# POWER.net
KiCad netlist of a schematic drawn in Altium Designer
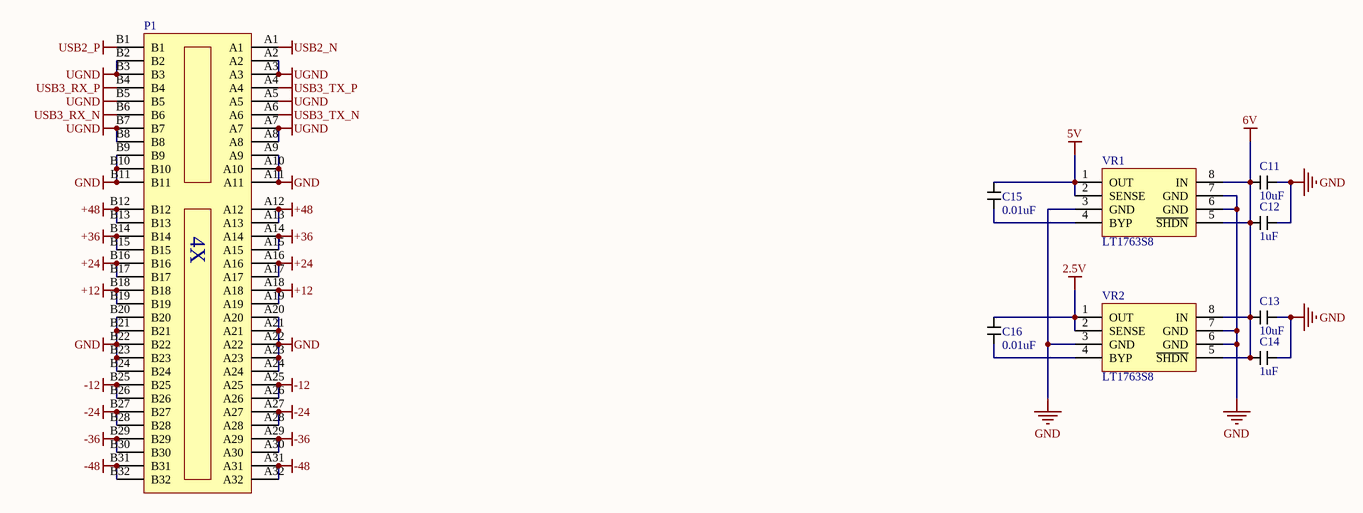
[diagram p0: POWER.SchDoc]

(export (version "E")
  (design (tool "Eeschema 10.0.6"))
  (components
    (comp (ref "C11") (value "10uF") (footprint "C0805") (libsource (lib "SMU") (part "C0805")))
    (comp (ref "C12") (value "1uF") (footprint "C0805") (libsource (lib "SMU") (part "C0805")))
    (comp (ref "C13") (value "10uF") (footprint "C0805") (libsource (lib "SMU") (part "C0805")))
    (comp (ref "C14") (value "1uF") (footprint "C0805") (libsource (lib "SMU") (part "C0805")))
    (comp (ref "C15") (value "0.01uF") (footprint "C0805") (libsource (lib "SMU") (part "C0805")))
    (comp (ref "C16") (value "0.01uF") (footprint "C0805") (libsource (lib "SMU") (part "C0805")))
    (comp (ref "P1")
      (value "10018783-10201TLF")
      (footprint "PCIe4X")
      (description "PCIe 4x")
      (libsource (lib "OpenSEM") (part "10018783-10201TLF"))
    )
    (comp (ref "VR1") (value "LT1763S8") (footprint "SOIC-8") (libsource (lib "OpenSEM") (part "LT1763S8")))
    (comp (ref "VR2") (value "LT1763S8") (footprint "SOIC-8") (libsource (lib "OpenSEM") (part "LT1763S8")))
  )
  (nets
    (net (code "1") (name "+12") (class "Default")
      (node (ref "P1") (pin "A18") (pinfunction "A18_A18") (pintype "passive"))
      (node (ref "P1") (pin "A19") (pinfunction "A19_A19") (pintype "passive"))
      (node (ref "P1") (pin "B18") (pinfunction "B18_B18") (pintype "passive"))
      (node (ref "P1") (pin "B19") (pinfunction "B19_B19") (pintype "passive"))
    )
    (net (code "2") (name "+24") (class "Default")
      (node (ref "P1") (pin "A16") (pinfunction "A16_A16") (pintype "passive"))
      (node (ref "P1") (pin "A17") (pinfunction "A17_A17") (pintype "passive"))
      (node (ref "P1") (pin "B16") (pinfunction "B16_B16") (pintype "passive"))
      (node (ref "P1") (pin "B17") (pinfunction "B17_B17") (pintype "passive"))
    )
    (net (code "3") (name "+36") (class "Default")
      (node (ref "P1") (pin "A14") (pinfunction "A14_A14") (pintype "passive"))
      (node (ref "P1") (pin "A15") (pinfunction "A15_A15") (pintype "passive"))
      (node (ref "P1") (pin "B14") (pinfunction "B14_B14") (pintype "passive"))
      (node (ref "P1") (pin "B15") (pinfunction "B15_B15") (pintype "passive"))
    )
    (net (code "4") (name "+48") (class "Default")
      (node (ref "P1") (pin "A12") (pinfunction "A12_A12") (pintype "passive"))
      (node (ref "P1") (pin "A13") (pinfunction "A13_A13") (pintype "passive"))
      (node (ref "P1") (pin "B12") (pinfunction "B12_B12") (pintype "passive"))
      (node (ref "P1") (pin "B13") (pinfunction "B13_B13") (pintype "passive"))
    )
    (net (code "5") (name "-12") (class "Default")
      (node (ref "P1") (pin "A25") (pinfunction "A25_A25") (pintype "passive"))
      (node (ref "P1") (pin "A26") (pinfunction "A26_A26") (pintype "passive"))
      (node (ref "P1") (pin "B25") (pinfunction "B25_B25") (pintype "passive"))
      (node (ref "P1") (pin "B26") (pinfunction "B26_B26") (pintype "passive"))
    )
    (net (code "6") (name "-24") (class "Default")
      (node (ref "P1") (pin "A27") (pinfunction "A27_A27") (pintype "passive"))
      (node (ref "P1") (pin "A28") (pinfunction "A28_A28") (pintype "passive"))
      (node (ref "P1") (pin "B27") (pinfunction "B27_B27") (pintype "passive"))
      (node (ref "P1") (pin "B28") (pinfunction "B28_B28") (pintype "passive"))
    )
    (net (code "7") (name "-36") (class "Default")
      (node (ref "P1") (pin "A29") (pinfunction "A29_A29") (pintype "passive"))
      (node (ref "P1") (pin "A30") (pinfunction "A30_A30") (pintype "passive"))
      (node (ref "P1") (pin "B29") (pinfunction "B29_B29") (pintype "passive"))
      (node (ref "P1") (pin "B30") (pinfunction "B30_B30") (pintype "passive"))
    )
    (net (code "8") (name "-48") (class "Default")
      (node (ref "P1") (pin "A31") (pinfunction "A31_A31") (pintype "passive"))
      (node (ref "P1") (pin "A32") (pinfunction "A32_A32") (pintype "passive"))
      (node (ref "P1") (pin "B31") (pinfunction "B31_B31") (pintype "passive"))
      (node (ref "P1") (pin "B32") (pinfunction "B32_B32") (pintype "passive"))
    )
    (net (code "9") (name "2.5V") (class "Default")
      (node (ref "C16") (pin "1") (pintype "passive"))
      (node (ref "VR2") (pin "1") (pinfunction "OUT_1") (pintype "passive"))
      (node (ref "VR2") (pin "2") (pinfunction "SENSE_2") (pintype "passive"))
    )
    (net (code "10") (name "5V") (class "Default")
      (node (ref "C15") (pin "1") (pintype "passive"))
      (node (ref "VR1") (pin "1") (pinfunction "OUT_1") (pintype "passive"))
      (node (ref "VR1") (pin "2") (pinfunction "SENSE_2") (pintype "passive"))
    )
    (net (code "11") (name "6V") (class "Default")
      (node (ref "C11") (pin "2") (pintype "passive"))
      (node (ref "C12") (pin "2") (pintype "passive"))
      (node (ref "C13") (pin "2") (pintype "passive"))
      (node (ref "C14") (pin "2") (pintype "passive"))
      (node (ref "VR1") (pin "5") (pinfunction "~{SHDN}_5") (pintype "passive"))
      (node (ref "VR1") (pin "8") (pinfunction "IN_8") (pintype "passive"))
      (node (ref "VR2") (pin "5") (pinfunction "~{SHDN}_5") (pintype "passive"))
      (node (ref "VR2") (pin "8") (pinfunction "IN_8") (pintype "passive"))
    )
    (net (code "12") (name "GND") (class "Default")
      (node (ref "C11") (pin "1") (pintype "passive"))
      (node (ref "C12") (pin "1") (pintype "passive"))
      (node (ref "C13") (pin "1") (pintype "passive"))
      (node (ref "C14") (pin "1") (pintype "passive"))
      (node (ref "P1") (pin "A10") (pinfunction "A10_A10") (pintype "passive"))
      (node (ref "P1") (pin "A11") (pinfunction "A11_A11") (pintype "passive"))
      (node (ref "P1") (pin "A20") (pinfunction "A20_A20") (pintype "passive"))
      (node (ref "P1") (pin "A21") (pinfunction "A21_A21") (pintype "passive"))
      (node (ref "P1") (pin "A22") (pinfunction "A22_A22") (pintype "passive"))
      (node (ref "P1") (pin "A23") (pinfunction "A23_A23") (pintype "passive"))
      (node (ref "P1") (pin "A24") (pinfunction "A24_A24") (pintype "passive"))
      (node (ref "P1") (pin "A9") (pinfunction "A9_A9") (pintype "passive"))
      (node (ref "P1") (pin "B10") (pinfunction "B10_B10") (pintype "passive"))
      (node (ref "P1") (pin "B11") (pinfunction "B11_B11") (pintype "passive"))
      (node (ref "P1") (pin "B20") (pinfunction "B20_B20") (pintype "passive"))
      (node (ref "P1") (pin "B21") (pinfunction "B21_B21") (pintype "passive"))
      (node (ref "P1") (pin "B22") (pinfunction "B22_B22") (pintype "passive"))
      (node (ref "P1") (pin "B23") (pinfunction "B23_B23") (pintype "passive"))
      (node (ref "P1") (pin "B24") (pinfunction "B24_B24") (pintype "passive"))
      (node (ref "P1") (pin "B9") (pinfunction "B9_B9") (pintype "passive"))
      (node (ref "VR1") (pin "3") (pinfunction "GND_3") (pintype "passive"))
      (node (ref "VR1") (pin "6") (pinfunction "GND_6") (pintype "passive"))
      (node (ref "VR1") (pin "7") (pinfunction "GND_7") (pintype "passive"))
      (node (ref "VR2") (pin "3") (pinfunction "GND_3") (pintype "passive"))
      (node (ref "VR2") (pin "6") (pinfunction "GND_6") (pintype "passive"))
      (node (ref "VR2") (pin "7") (pinfunction "GND_7") (pintype "passive"))
    )
    (net (code "13") (name "Net-(VR1-BYP)") (class "Default")
      (node (ref "C15") (pin "2") (pintype "passive"))
      (node (ref "VR1") (pin "4") (pinfunction "BYP_4") (pintype "passive"))
    )
    (net (code "14") (name "Net-(VR2-BYP)") (class "Default")
      (node (ref "C16") (pin "2") (pintype "passive"))
      (node (ref "VR2") (pin "4") (pinfunction "BYP_4") (pintype "passive"))
    )
    (net (code "15") (name "UGND") (class "Default")
      (node (ref "P1") (pin "A2") (pinfunction "A2_A2") (pintype "passive"))
      (node (ref "P1") (pin "A3") (pinfunction "A3_A3") (pintype "passive"))
      (node (ref "P1") (pin "A5") (pinfunction "A5_A5") (pintype "passive"))
      (node (ref "P1") (pin "A7") (pinfunction "A7_A7") (pintype "passive"))
      (node (ref "P1") (pin "A8") (pinfunction "A8_A8") (pintype "passive"))
      (node (ref "P1") (pin "B2") (pinfunction "B2_B2") (pintype "passive"))
      (node (ref "P1") (pin "B3") (pinfunction "B3_B3") (pintype "passive"))
      (node (ref "P1") (pin "B5") (pinfunction "B5_B5") (pintype "passive"))
      (node (ref "P1") (pin "B7") (pinfunction "B7_B7") (pintype "passive"))
      (node (ref "P1") (pin "B8") (pinfunction "B8_B8") (pintype "passive"))
    )
    (net (code "16") (name "USB2_N") (class "Default")
      (node (ref "P1") (pin "A1") (pinfunction "A1_A1") (pintype "passive"))
    )
    (net (code "17") (name "USB2_P") (class "Default")
      (node (ref "P1") (pin "B1") (pinfunction "B1_B1") (pintype "passive"))
    )
    (net (code "18") (name "USB3_RX_N") (class "Default")
      (node (ref "P1") (pin "B6") (pinfunction "B6_B6") (pintype "passive"))
    )
    (net (code "19") (name "USB3_RX_P") (class "Default")
      (node (ref "P1") (pin "B4") (pinfunction "B4_B4") (pintype "passive"))
    )
    (net (code "20") (name "USB3_TX_N") (class "Default")
      (node (ref "P1") (pin "A6") (pinfunction "A6_A6") (pintype "passive"))
    )
    (net (code "21") (name "USB3_TX_P") (class "Default")
      (node (ref "P1") (pin "A4") (pinfunction "A4_A4") (pintype "passive"))
    )
  )
)
